# sch_Camera.net
KiCad netlist of a schematic drawn in Altium Designer
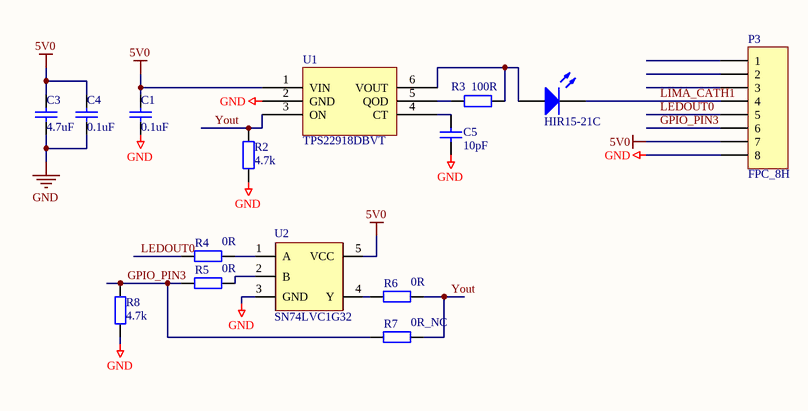
[diagram p0: sch_Camera.SchDoc]

(export (version "E")
  (design (tool "Eeschema 10.0.6"))
  (components
    (comp (ref "C1")
      (value "0.1uF")
      (footprint "0603C_N")
      (description "Capacitor")
      (fields (field (name "PUBLISHER") "Altium Limited"))
      (libsource (lib "Miscellaneous Devices") (part "Cap"))
    )
    (comp (ref "C3")
      (value "4.7uF")
      (footprint "0603R_N")
      (description "Capacitor")
      (fields (field (name "PUBLISHER") "Altium Limited"))
      (libsource (lib "Miscellaneous Devices") (part "Cap"))
    )
    (comp (ref "C4")
      (value "0.1uF")
      (footprint "0603C_N")
      (description "Capacitor")
      (fields (field (name "PUBLISHER") "Altium Limited"))
      (libsource (lib "Miscellaneous Devices") (part "Cap"))
    )
    (comp (ref "C5")
      (value "10pF")
      (footprint "0603C_N")
      (description "Capacitor")
      (fields (field (name "PUBLISHER") "Altium Limited"))
      (libsource (lib "Miscellaneous Devices") (part "Cap"))
    )
    (comp (ref "HIR15-21C")
      (value "LIMA")
      (footprint "1206R")
      (description "发光二级管")
      (libsource (lib "TXW") (part "LED"))
    )
    (comp (ref "P3")
      (value "FPC_8H")
      (footprint "FPC_8H")
      (description "Header, 8-Pin, Right Angle")
      (fields (field (name "PUBLISHER") "Altium Limited"))
      (libsource (lib "Miscellaneous Connectors") (part "Header 8H"))
    )
    (comp (ref "R2")
      (value "4.7k")
      (footprint "0603R_N")
      (description "Resistor")
      (fields (field (name "PUBLISHER") "Altium Limited"))
      (libsource (lib "SZG") (part "Resistor"))
    )
    (comp (ref "R3")
      (value "100R")
      (footprint "0603R_N")
      (description "Resistor")
      (fields (field (name "PUBLISHER") "Altium Limited"))
      (libsource (lib "") (part "Resistor_1"))
    )
    (comp (ref "R4")
      (value "0R")
      (footprint "0603R_N")
      (description "Resistor")
      (fields (field (name "PUBLISHER") "Altium Limited"))
      (libsource (lib "") (part "Resistor_1"))
    )
    (comp (ref "R5")
      (value "0R")
      (footprint "0603R_N")
      (description "Resistor")
      (fields (field (name "PUBLISHER") "Altium Limited"))
      (libsource (lib "") (part "Resistor_1"))
    )
    (comp (ref "R6")
      (value "0R")
      (footprint "0603R_N")
      (description "Resistor")
      (fields (field (name "PUBLISHER") "Altium Limited"))
      (libsource (lib "") (part "Resistor_1"))
    )
    (comp (ref "R7")
      (value "0R_NC")
      (footprint "0603R_N")
      (description "Resistor")
      (fields (field (name "PUBLISHER") "Altium Limited"))
      (libsource (lib "") (part "Resistor_1"))
    )
    (comp (ref "R8")
      (value "4.7k")
      (footprint "0603R_N")
      (description "Resistor")
      (fields (field (name "PUBLISHER") "Altium Limited"))
      (libsource (lib "SZG") (part "Resistor"))
    )
    (comp (ref "U1")
      (value "TPS22918DBVT")
      (footprint "SOT23-6_P0.95X2.4_L3W4.2H1.1")
      (libsource (lib "SZG") (part "TPS22918DBVT"))
    )
    (comp (ref "U2")
      (value "SN74LVC1G32")
      (footprint "SOT23-5_P0.95X2.4_L3W4.2H1.1")
      (libsource (lib "SZG") (part "SN74LVC1G32"))
    )
  )
  (nets
    (net (code "1") (name "/GPIO_PIN3") (class "Default")
      (node (ref "P3") (pin "6") (pinfunction "6_6") (pintype "passive"))
      (node (ref "R5") (pin "2") (pinfunction "2_2") (pintype "passive"))
      (node (ref "R7") (pin "2") (pinfunction "2_2") (pintype "passive"))
      (node (ref "R8") (pin "2") (pinfunction "2_2") (pintype "passive"))
    )
    (net (code "2") (name "/LEDOUT0") (class "Default")
      (node (ref "P3") (pin "5") (pinfunction "5_5") (pintype "passive"))
      (node (ref "R4") (pin "2") (pinfunction "2_2") (pintype "passive"))
    )
    (net (code "3") (name "/LIMA_CATH1") (class "Default")
      (node (ref "HIR15-21C") (pin "2") (pinfunction "K_2") (pintype "passive"))
      (node (ref "P3") (pin "4") (pinfunction "4_4") (pintype "passive"))
    )
    (net (code "4") (name "/Yout") (class "Default")
      (node (ref "R2") (pin "2") (pinfunction "2_2") (pintype "passive"))
      (node (ref "R6") (pin "1") (pinfunction "1_1") (pintype "passive"))
      (node (ref "R7") (pin "1") (pinfunction "1_1") (pintype "passive"))
      (node (ref "U1") (pin "3") (pinfunction "ON_3") (pintype "passive"))
    )
    (net (code "5") (name "5V0") (class "Default")
      (node (ref "C1") (pin "2") (pinfunction "2_2") (pintype "passive"))
      (node (ref "C3") (pin "2") (pinfunction "2_2") (pintype "passive"))
      (node (ref "C4") (pin "2") (pinfunction "2_2") (pintype "passive"))
      (node (ref "P3") (pin "7") (pinfunction "7_7") (pintype "passive"))
      (node (ref "U1") (pin "1") (pinfunction "VIN_1") (pintype "passive"))
      (node (ref "U2") (pin "5") (pinfunction "VCC_5") (pintype "passive"))
    )
    (net (code "6") (name "GND") (class "Default")
      (node (ref "C1") (pin "1") (pinfunction "1_1") (pintype "passive"))
      (node (ref "C3") (pin "1") (pinfunction "1_1") (pintype "passive"))
      (node (ref "C4") (pin "1") (pinfunction "1_1") (pintype "passive"))
      (node (ref "C5") (pin "1") (pinfunction "1_1") (pintype "passive"))
      (node (ref "P3") (pin "8") (pinfunction "8_8") (pintype "passive"))
      (node (ref "R2") (pin "1") (pinfunction "1_1") (pintype "passive"))
      (node (ref "R8") (pin "1") (pinfunction "1_1") (pintype "passive"))
      (node (ref "U1") (pin "2") (pinfunction "GND_2") (pintype "passive"))
      (node (ref "U2") (pin "3") (pinfunction "GND_3") (pintype "passive"))
    )
    (net (code "7") (name "Net-(HIR15-21C-A)") (class "Default")
      (node (ref "HIR15-21C") (pin "1") (pinfunction "A_1") (pintype "passive"))
      (node (ref "R3") (pin "1") (pinfunction "1_1") (pintype "passive"))
      (node (ref "U1") (pin "6") (pinfunction "VOUT_6") (pintype "passive"))
    )
    (net (code "8") (name "Net-(U1-CT)") (class "Default")
      (node (ref "C5") (pin "2") (pinfunction "2_2") (pintype "passive"))
      (node (ref "U1") (pin "4") (pinfunction "CT_4") (pintype "passive"))
    )
    (net (code "9") (name "Net-(U1-QOD)") (class "Default")
      (node (ref "R3") (pin "2") (pinfunction "2_2") (pintype "passive"))
      (node (ref "U1") (pin "5") (pinfunction "QOD_5") (pintype "passive"))
    )
    (net (code "10") (name "Net-(U2-A)") (class "Default")
      (node (ref "R4") (pin "1") (pinfunction "1_1") (pintype "passive"))
      (node (ref "U2") (pin "1") (pinfunction "A_1") (pintype "passive"))
    )
    (net (code "11") (name "Net-(U2-B)") (class "Default")
      (node (ref "R5") (pin "1") (pinfunction "1_1") (pintype "passive"))
      (node (ref "U2") (pin "2") (pinfunction "B_2") (pintype "passive"))
    )
    (net (code "12") (name "Net-(U2-Y)") (class "Default")
      (node (ref "R6") (pin "2") (pinfunction "2_2") (pintype "passive"))
      (node (ref "U2") (pin "4") (pinfunction "Y_4") (pintype "passive"))
    )
    (net (code "13") (name "unconnected-(P3-Pad1)") (class "Default")
      (node (ref "P3") (pin "1") (pinfunction "1_1") (pintype "passive"))
    )
    (net (code "14") (name "unconnected-(P3-Pad2)") (class "Default")
      (node (ref "P3") (pin "2") (pinfunction "2_2") (pintype "passive"))
    )
    (net (code "15") (name "unconnected-(P3-Pad3)") (class "Default")
      (node (ref "P3") (pin "3") (pinfunction "3_3") (pintype "passive"))
    )
  )
)
